# Flash_Memory.net
KiCad netlist of a schematic drawn in Altium Designer
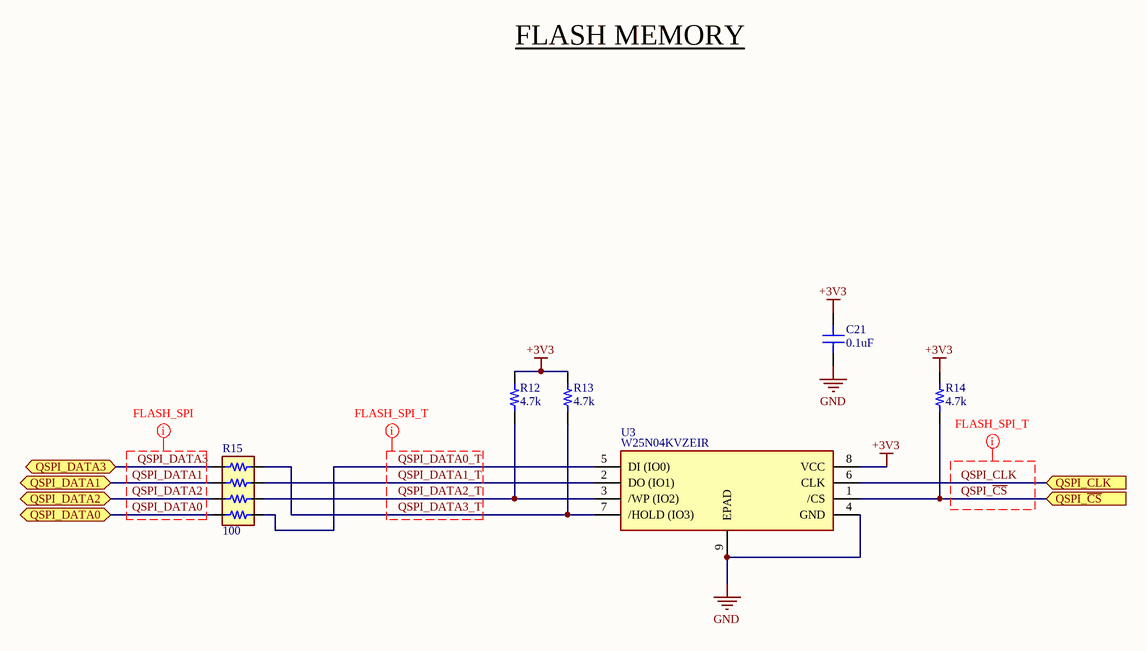
[diagram p0: Flash_Memory.SchDoc]

(export (version "E")
  (design (tool "Eeschema 10.0.6"))
  (components
    (comp (ref "C21")
      (value "0.1uF")
      (footprint "CAP0402")
      (description "CAP CER 0.1uF 16V X7R 0402 10%")
      (fields (field (name "TOLERANCE") "10%") (field (name "VOLTAGE") "16V"))
      (libsource (lib "Pasivos") (part "C0402C104K4RAC"))
    )
    (comp (ref "R12")
      (value "4.7k")
      (footprint "RES0402")
      (description "RES SMD 4.7K OHM 1% 0.063W 0402")
      (fields (field (name "POWER") "0.063 W") (field (name "MANUFACTURER") "Vishay"))
      (libsource (lib "Pasivos") (part "CRCW04024K70FK"))
    )
    (comp (ref "R13")
      (value "4.7k")
      (footprint "RES0402")
      (description "RES SMD 4.7K OHM 1% 0.063W 0402")
      (fields (field (name "POWER") "0.063 W") (field (name "MANUFACTURER") "Vishay"))
      (libsource (lib "Pasivos") (part "CRCW04024K70FK"))
    )
    (comp (ref "R14")
      (value "4.7k")
      (footprint "RES0402")
      (description "RES SMD 4.7K OHM 1% 0.063W 0402")
      (fields (field (name "POWER") "0.063 W") (field (name "MANUFACTURER") "Vishay"))
      (libsource (lib "Pasivos") (part "CRCW04024K70FK"))
    )
    (comp (ref "R15")
      (value "100")
      (footprint "ArrayResistor-1206")
      (description "RES ARRAY 4 RES 100 OHM 1206")
      (fields (field (name "MANUFACTURER") "Panasonic") (field (name "PARTNUMBER") "EXB-38V101JV"))
      (libsource (lib "Pasivos") (part "EXB-38V101JV"))
    )
    (comp (ref "U3")
      (value "W25N04KVZEIR")
      (footprint "WSON-8")
      (description "QSPINAND 4G-BIT FLASH MEMORY WITH DUAL/QUAD SPI BUFFER READ & SEQUENTIAL READ")
      (fields (field (name "MANUFACTURER") "Winbond"))
      (libsource (lib "Integrated_Circuits") (part "W25N04KVZEIR"))
    )
  )
  (nets
    (net (code "1") (name "+3V3") (class "Default")
      (node (ref "C21") (pin "2") (pinfunction "2_2") (pintype "passive"))
      (node (ref "R12") (pin "2") (pinfunction "2_2") (pintype "passive"))
      (node (ref "R13") (pin "2") (pinfunction "2_2") (pintype "passive"))
      (node (ref "R14") (pin "2") (pinfunction "2_2") (pintype "passive"))
      (node (ref "U3") (pin "8") (pinfunction "VCC_8") (pintype "power_in"))
    )
    (net (code "2") (name "/QSPI_CLK") (class "Default")
      (node (ref "U3") (pin "6") (pinfunction "CLK_6") (pintype "passive"))
    )
    (net (code "3") (name "/QSPI_DATA0") (class "Default")
      (node (ref "R15") (pin "4") (pinfunction "4_4") (pintype "passive"))
    )
    (net (code "4") (name "/QSPI_DATA0_T") (class "Default")
      (node (ref "R15") (pin "5") (pinfunction "5_5") (pintype "passive"))
      (node (ref "U3") (pin "5") (pinfunction "DI_(IO0)_5") (pintype "passive"))
    )
    (net (code "5") (name "/QSPI_DATA1") (class "Default")
      (node (ref "R15") (pin "2") (pinfunction "2_2") (pintype "passive"))
    )
    (net (code "6") (name "/QSPI_DATA1_T") (class "Default")
      (node (ref "R15") (pin "7") (pinfunction "7_7") (pintype "passive"))
      (node (ref "U3") (pin "2") (pinfunction "DO_(IO1)_2") (pintype "passive"))
    )
    (net (code "7") (name "/QSPI_DATA2") (class "Default")
      (node (ref "R15") (pin "3") (pinfunction "3_3") (pintype "passive"))
    )
    (net (code "8") (name "/QSPI_DATA2_T") (class "Default")
      (node (ref "R12") (pin "1") (pinfunction "1_1") (pintype "passive"))
      (node (ref "R15") (pin "6") (pinfunction "6_6") (pintype "passive"))
      (node (ref "U3") (pin "3") (pinfunction "/WP_(IO2)_3") (pintype "passive"))
    )
    (net (code "9") (name "/QSPI_DATA3") (class "Default")
      (node (ref "R15") (pin "1") (pinfunction "1_1") (pintype "passive"))
    )
    (net (code "10") (name "/QSPI_DATA3_T") (class "Default")
      (node (ref "R13") (pin "1") (pinfunction "1_1") (pintype "passive"))
      (node (ref "R15") (pin "8") (pinfunction "8_8") (pintype "passive"))
      (node (ref "U3") (pin "7") (pinfunction "/HOLD_(IO3)_7") (pintype "passive"))
    )
    (net (code "11") (name "/QSPI_~{CS}") (class "Default")
      (node (ref "R14") (pin "1") (pinfunction "1_1") (pintype "passive"))
      (node (ref "U3") (pin "1") (pinfunction "/CS_1") (pintype "passive"))
    )
    (net (code "12") (name "GND") (class "Default")
      (node (ref "C21") (pin "1") (pinfunction "1_1") (pintype "passive"))
      (node (ref "U3") (pin "4") (pinfunction "GND_4") (pintype "power_in"))
      (node (ref "U3") (pin "9") (pinfunction "EPAD_9") (pintype "passive"))
    )
  )
)
